# SCHM_LM2596.net
KiCad netlist of a schematic drawn in Altium Designer
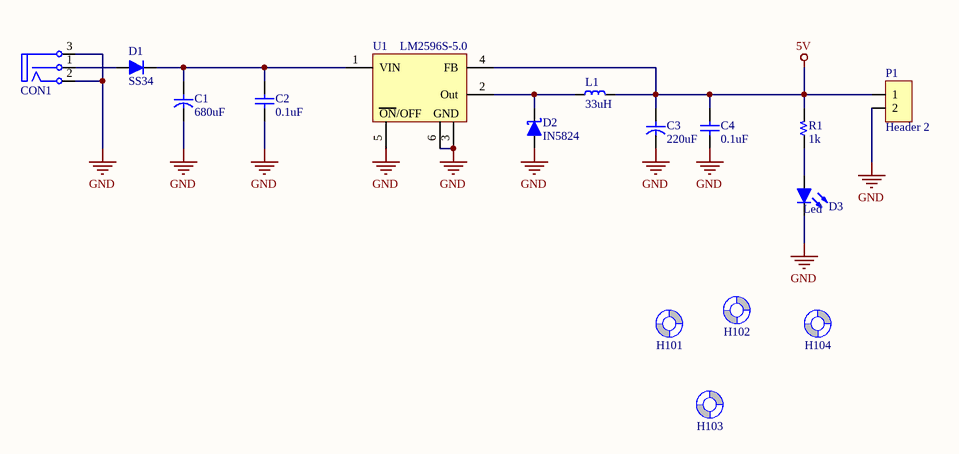
[diagram p0: SCHM_LM2596.SchDoc]

(export (version "E")
  (design (tool "Eeschema 10.0.6"))
  (components
    (comp (ref "C1")
      (value "680uF")
      (footprint "CYL/D.500/LS.200")
      (description "Capacitor pol")
      (libsource (lib "chipfc_altium_libs") (part "Capacitor"))
    )
    (comp (ref "C2")
      (value "0.1uF")
      (footprint "C 0805")
      (description "Capacitor non-pol")
      (libsource (lib "chipfc_altium_libs") (part "Capacitor NP"))
    )
    (comp (ref "C3")
      (value "220uF")
      (footprint "CYL/D.500/LS.200")
      (description "Capacitor pol")
      (libsource (lib "chipfc_altium_libs") (part "Capacitor"))
    )
    (comp (ref "C4")
      (value "0.1uF")
      (footprint "C 0805")
      (description "Capacitor non-pol")
      (libsource (lib "chipfc_altium_libs") (part "Capacitor NP"))
    )
    (comp (ref "CON1")
      (value "CON DC PWR")
      (footprint "CONN/DC/PWR/5.0MM")
      (description "DC input connector")
      (libsource (lib "chipfc_altium_libs") (part "CON DC PWR"))
    )
    (comp (ref "D1")
      (value "SS34")
      (footprint "DO-214AC (SMA)")
      (description "Default Diode")
      (libsource (lib "chipfc_altium_libs") (part "Diode"))
    )
    (comp (ref "D2")
      (value "IN5824")
      (footprint "DO-214AC (SMA)")
      (description "Schottky Diode")
      (libsource (lib "chipfc_altium_libs") (part "Diode Schottky"))
    )
    (comp (ref "D3")
      (value "Led")
      (footprint "Led 0805 RED")
      (description "Typical LED")
      (libsource (lib "chipfc_altium_libs") (part "Led"))
    )
    (comp (ref "H101")
      (value "Screw Hole")
      (footprint "SCREW/3.2/7.0/M")
      (libsource (lib "chipfc_altium_libs") (part "Screw Hole"))
    )
    (comp (ref "H102")
      (value "Screw Hole")
      (footprint "SCREW/3.2/7.0/M")
      (libsource (lib "chipfc_altium_libs") (part "Screw Hole"))
    )
    (comp (ref "H103")
      (value "Screw Hole")
      (footprint "SCREW/3.2/7.0/M")
      (libsource (lib "chipfc_altium_libs") (part "Screw Hole"))
    )
    (comp (ref "H104")
      (value "Screw Hole")
      (footprint "SCREW/3.2/7.0/M")
      (libsource (lib "chipfc_altium_libs") (part "Screw Hole"))
    )
    (comp (ref "L1")
      (value "33uH")
      (footprint "Inductor SMD 12x12x8")
      (description "Inductor")
      (libsource (lib "chipfc_altium_libs") (part "Inductor"))
    )
    (comp (ref "P1")
      (value "Header 2")
      (footprint "HDR/Header/2/VH")
      (description "Header, 2-Pin")
      (libsource (lib "chipfc_altium_libs") (part "Header 2"))
    )
    (comp (ref "R1")
      (value "1k")
      (footprint "R 0805")
      (description "Resistor")
      (libsource (lib "chipfc_altium_libs") (part "Resistor"))
    )
    (comp (ref "U1")
      (value "LM2596S-5.0")
      (footprint "TO-263-5")
      (description "Simple Switcher 3A Step-Down Voltage Regulator")
      (libsource (lib "chipfc_altium_libs") (part "LM2596S-5.0"))
    )
  )
  (nets
    (net (code "1") (name "5V") (class "Default")
      (node (ref "C3") (pin "1") (pinfunction "1_1") (pintype "passive"))
      (node (ref "C4") (pin "1") (pinfunction "1_1") (pintype "passive"))
      (node (ref "L1") (pin "2") (pinfunction "2_2") (pintype "passive"))
      (node (ref "P1") (pin "1") (pinfunction "1_1") (pintype "passive"))
      (node (ref "R1") (pin "2") (pinfunction "2_2") (pintype "passive"))
      (node (ref "U1") (pin "4") (pinfunction "FB_4") (pintype "passive"))
    )
    (net (code "2") (name "GND") (class "Default")
      (node (ref "C1") (pin "2") (pinfunction "2_2") (pintype "passive"))
      (node (ref "C2") (pin "2") (pinfunction "2_2") (pintype "passive"))
      (node (ref "C3") (pin "2") (pinfunction "2_2") (pintype "passive"))
      (node (ref "C4") (pin "2") (pinfunction "2_2") (pintype "passive"))
      (node (ref "CON1") (pin "2") (pinfunction "T_2") (pintype "passive"))
      (node (ref "CON1") (pin "3") (pinfunction "TN_3") (pintype "passive"))
      (node (ref "D2") (pin "1") (pinfunction "A_1") (pintype "passive"))
      (node (ref "D3") (pin "2") (pinfunction "K_2") (pintype "passive"))
      (node (ref "P1") (pin "2") (pinfunction "2_2") (pintype "passive"))
      (node (ref "U1") (pin "3") (pinfunction "GND_3") (pintype "passive"))
      (node (ref "U1") (pin "5") (pinfunction "~{ON}/OFF_5") (pintype "passive"))
      (node (ref "U1") (pin "6") (pinfunction "PAD_6") (pintype "passive"))
    )
    (net (code "3") (name "Net-(CON1-S)") (class "Default")
      (node (ref "CON1") (pin "1") (pinfunction "S_1") (pintype "power_in"))
      (node (ref "D1") (pin "1") (pinfunction "A_1") (pintype "passive"))
    )
    (net (code "4") (name "Net-(D1-K)") (class "Default")
      (node (ref "C1") (pin "1") (pinfunction "1_1") (pintype "passive"))
      (node (ref "C2") (pin "1") (pinfunction "1_1") (pintype "passive"))
      (node (ref "D1") (pin "2") (pinfunction "K_2") (pintype "passive"))
      (node (ref "U1") (pin "1") (pinfunction "VIN_1") (pintype "passive"))
    )
    (net (code "5") (name "Net-(D2-K)") (class "Default")
      (node (ref "D2") (pin "2") (pinfunction "K_2") (pintype "passive"))
      (node (ref "L1") (pin "1") (pinfunction "1_1") (pintype "passive"))
      (node (ref "U1") (pin "2") (pinfunction "Out_2") (pintype "passive"))
    )
    (net (code "6") (name "Net-(D3-A)") (class "Default")
      (node (ref "D3") (pin "1") (pinfunction "A_1") (pintype "passive"))
      (node (ref "R1") (pin "1") (pinfunction "1_1") (pintype "passive"))
    )
    (net (code "7") (name "unconnected-(H101-Screw-Pad1)") (class "Default")
      (node (ref "H101") (pin "1") (pinfunction "Screw_1") (pintype "passive"))
    )
    (net (code "8") (name "unconnected-(H102-Screw-Pad1)") (class "Default")
      (node (ref "H102") (pin "1") (pinfunction "Screw_1") (pintype "passive"))
    )
    (net (code "9") (name "unconnected-(H103-Screw-Pad1)") (class "Default")
      (node (ref "H103") (pin "1") (pinfunction "Screw_1") (pintype "passive"))
    )
    (net (code "10") (name "unconnected-(H104-Screw-Pad1)") (class "Default")
      (node (ref "H104") (pin "1") (pinfunction "Screw_1") (pintype "passive"))
    )
  )
)
